# CameraConn.net
KiCad netlist of a schematic drawn in Altium Designer
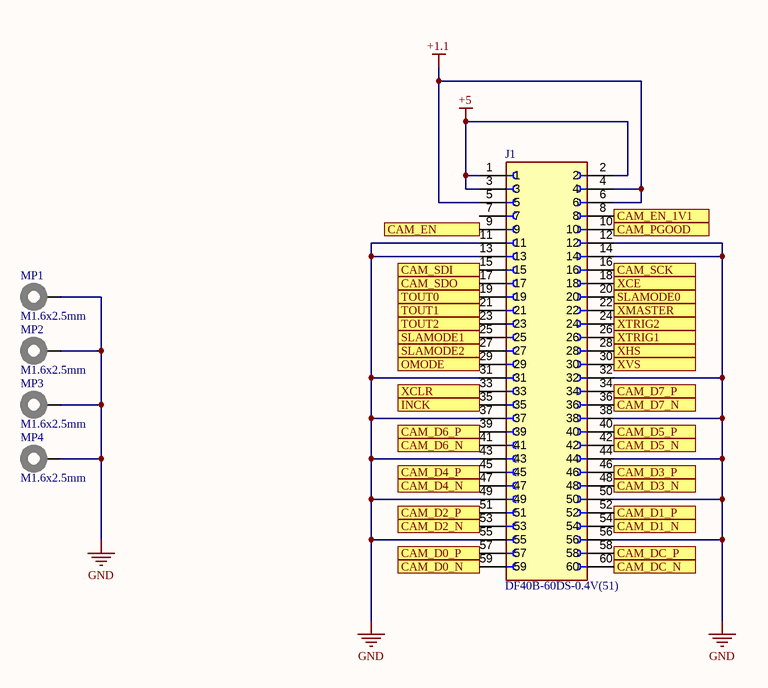
[diagram p0: CameraConn.SchDoc]

(export (version "E")
  (design (tool "Eeschema 10.0.6"))
  (components
    (comp (ref "J1")
      (value "DF40B-60DS-0.4V(51)")
      (footprint "HRS_DF40B-60DS-0.4V(51)")
      (fields (field (name "MF") "{'manufacturer': u'Hirose Electric Co Ltd'}"))
      (libsource (lib "SimulaVR") (part "DF40B-60DS-0.4V(51)"))
    )
    (comp (ref "MP1")
      (value "M1.6x2.5mm")
      (footprint "97730256330")
      (description "WA-SMSI SMT Steel Spacer, internal Thread Bottom closed, OD 3.3mm, M1.6x2.5mm")
      (fields
        (field (name "MANUFACTURER PART NUMBER") "97730256330")
        (field (name "MANUFACTURER") "Wurth Elektronik")
      )
      (libsource (lib "Altium_WA-SMSI (rev21a)") (part "97730256330"))
    )
    (comp (ref "MP2")
      (value "M1.6x2.5mm")
      (footprint "97730256330")
      (description "WA-SMSI SMT Steel Spacer, internal Thread Bottom closed, OD 3.3mm, M1.6x2.5mm")
      (fields
        (field (name "MANUFACTURER PART NUMBER") "97730256330")
        (field (name "MANUFACTURER") "Wurth Elektronik")
      )
      (libsource (lib "Altium_WA-SMSI (rev21a)") (part "97730256330"))
    )
    (comp (ref "MP3")
      (value "M1.6x2.5mm")
      (footprint "97730256330")
      (description "WA-SMSI SMT Steel Spacer, internal Thread Bottom closed, OD 3.3mm, M1.6x2.5mm")
      (fields
        (field (name "MANUFACTURER PART NUMBER") "97730256330")
        (field (name "MANUFACTURER") "Wurth Elektronik")
      )
      (libsource (lib "Altium_WA-SMSI (rev21a)") (part "97730256330"))
    )
    (comp (ref "MP4")
      (value "M1.6x2.5mm")
      (footprint "97730256330")
      (description "WA-SMSI SMT Steel Spacer, internal Thread Bottom closed, OD 3.3mm, M1.6x2.5mm")
      (fields
        (field (name "MANUFACTURER PART NUMBER") "97730256330")
        (field (name "MANUFACTURER") "Wurth Elektronik")
      )
      (libsource (lib "Altium_WA-SMSI (rev21a)") (part "97730256330"))
    )
  )
  (nets
    (net (code "1") (name "+1.1") (class "Default")
      (node (ref "J1") (pin "4") (pinfunction "4_4") (pintype "passive"))
      (node (ref "J1") (pin "5") (pinfunction "5_5") (pintype "passive"))
      (node (ref "J1") (pin "6") (pinfunction "6_6") (pintype "passive"))
    )
    (net (code "2") (name "+5") (class "Default")
      (node (ref "J1") (pin "1") (pinfunction "1_1") (pintype "passive"))
      (node (ref "J1") (pin "2") (pinfunction "2_2") (pintype "passive"))
      (node (ref "J1") (pin "3") (pinfunction "3_3") (pintype "passive"))
    )
    (net (code "3") (name "/CAM_D0_N") (class "Default")
      (node (ref "J1") (pin "59") (pinfunction "59_59") (pintype "passive"))
    )
    (net (code "4") (name "/CAM_D0_P") (class "Default")
      (node (ref "J1") (pin "57") (pinfunction "57_57") (pintype "passive"))
    )
    (net (code "5") (name "/CAM_D1_N") (class "Default")
      (node (ref "J1") (pin "54") (pinfunction "54_54") (pintype "passive"))
    )
    (net (code "6") (name "/CAM_D1_P") (class "Default")
      (node (ref "J1") (pin "52") (pinfunction "52_52") (pintype "passive"))
    )
    (net (code "7") (name "/CAM_D2_N") (class "Default")
      (node (ref "J1") (pin "53") (pinfunction "53_53") (pintype "passive"))
    )
    (net (code "8") (name "/CAM_D2_P") (class "Default")
      (node (ref "J1") (pin "51") (pinfunction "51_51") (pintype "passive"))
    )
    (net (code "9") (name "/CAM_D3_N") (class "Default")
      (node (ref "J1") (pin "48") (pinfunction "48_48") (pintype "passive"))
    )
    (net (code "10") (name "/CAM_D3_P") (class "Default")
      (node (ref "J1") (pin "46") (pinfunction "46_46") (pintype "passive"))
    )
    (net (code "11") (name "/CAM_D4_N") (class "Default")
      (node (ref "J1") (pin "47") (pinfunction "47_47") (pintype "passive"))
    )
    (net (code "12") (name "/CAM_D4_P") (class "Default")
      (node (ref "J1") (pin "45") (pinfunction "45_45") (pintype "passive"))
    )
    (net (code "13") (name "/CAM_D5_N") (class "Default")
      (node (ref "J1") (pin "42") (pinfunction "42_42") (pintype "passive"))
    )
    (net (code "14") (name "/CAM_D5_P") (class "Default")
      (node (ref "J1") (pin "40") (pinfunction "40_40") (pintype "passive"))
    )
    (net (code "15") (name "/CAM_D6_N") (class "Default")
      (node (ref "J1") (pin "41") (pinfunction "41_41") (pintype "passive"))
    )
    (net (code "16") (name "/CAM_D6_P") (class "Default")
      (node (ref "J1") (pin "39") (pinfunction "39_39") (pintype "passive"))
    )
    (net (code "17") (name "/CAM_D7_N") (class "Default")
      (node (ref "J1") (pin "36") (pinfunction "36_36") (pintype "passive"))
    )
    (net (code "18") (name "/CAM_D7_P") (class "Default")
      (node (ref "J1") (pin "34") (pinfunction "34_34") (pintype "passive"))
    )
    (net (code "19") (name "/CAM_DC_N") (class "Default")
      (node (ref "J1") (pin "60") (pinfunction "60_60") (pintype "passive"))
    )
    (net (code "20") (name "/CAM_DC_P") (class "Default")
      (node (ref "J1") (pin "58") (pinfunction "58_58") (pintype "passive"))
    )
    (net (code "21") (name "/CAM_EN") (class "Default")
      (node (ref "J1") (pin "9") (pinfunction "9_9") (pintype "passive"))
    )
    (net (code "22") (name "/CAM_EN_1V1") (class "Default")
      (node (ref "J1") (pin "8") (pinfunction "8_8") (pintype "passive"))
    )
    (net (code "23") (name "/CAM_PGOOD") (class "Default")
      (node (ref "J1") (pin "10") (pinfunction "10_10") (pintype "passive"))
    )
    (net (code "24") (name "/CAM_SCK") (class "Default")
      (node (ref "J1") (pin "16") (pinfunction "16_16") (pintype "passive"))
    )
    (net (code "25") (name "/CAM_SDI") (class "Default")
      (node (ref "J1") (pin "15") (pinfunction "15_15") (pintype "passive"))
    )
    (net (code "26") (name "/CAM_SDO") (class "Default")
      (node (ref "J1") (pin "17") (pinfunction "17_17") (pintype "passive"))
    )
    (net (code "27") (name "/INCK") (class "Default")
      (node (ref "J1") (pin "35") (pinfunction "35_35") (pintype "passive"))
    )
    (net (code "28") (name "/OMODE") (class "Default")
      (node (ref "J1") (pin "29") (pinfunction "29_29") (pintype "passive"))
    )
    (net (code "29") (name "/SLAMODE0") (class "Default")
      (node (ref "J1") (pin "20") (pinfunction "20_20") (pintype "passive"))
    )
    (net (code "30") (name "/SLAMODE1") (class "Default")
      (node (ref "J1") (pin "25") (pinfunction "25_25") (pintype "passive"))
    )
    (net (code "31") (name "/SLAMODE2") (class "Default")
      (node (ref "J1") (pin "27") (pinfunction "27_27") (pintype "passive"))
    )
    (net (code "32") (name "/TOUT0") (class "Default")
      (node (ref "J1") (pin "19") (pinfunction "19_19") (pintype "passive"))
    )
    (net (code "33") (name "/TOUT1") (class "Default")
      (node (ref "J1") (pin "21") (pinfunction "21_21") (pintype "passive"))
    )
    (net (code "34") (name "/TOUT2") (class "Default")
      (node (ref "J1") (pin "23") (pinfunction "23_23") (pintype "passive"))
    )
    (net (code "35") (name "/XCE") (class "Default")
      (node (ref "J1") (pin "18") (pinfunction "18_18") (pintype "passive"))
    )
    (net (code "36") (name "/XCLR") (class "Default")
      (node (ref "J1") (pin "33") (pinfunction "33_33") (pintype "passive"))
    )
    (net (code "37") (name "/XHS") (class "Default")
      (node (ref "J1") (pin "28") (pinfunction "28_28") (pintype "passive"))
    )
    (net (code "38") (name "/XMASTER") (class "Default")
      (node (ref "J1") (pin "22") (pinfunction "22_22") (pintype "passive"))
    )
    (net (code "39") (name "/XTRIG1") (class "Default")
      (node (ref "J1") (pin "26") (pinfunction "26_26") (pintype "passive"))
    )
    (net (code "40") (name "/XTRIG2") (class "Default")
      (node (ref "J1") (pin "24") (pinfunction "24_24") (pintype "passive"))
    )
    (net (code "41") (name "/XVS") (class "Default")
      (node (ref "J1") (pin "30") (pinfunction "30_30") (pintype "passive"))
    )
    (net (code "42") (name "GND") (class "Default")
      (node (ref "J1") (pin "11") (pinfunction "11_11") (pintype "passive"))
      (node (ref "J1") (pin "12") (pinfunction "12_12") (pintype "passive"))
      (node (ref "J1") (pin "13") (pinfunction "13_13") (pintype "passive"))
      (node (ref "J1") (pin "14") (pinfunction "14_14") (pintype "passive"))
      (node (ref "J1") (pin "31") (pinfunction "31_31") (pintype "passive"))
      (node (ref "J1") (pin "32") (pinfunction "32_32") (pintype "passive"))
      (node (ref "J1") (pin "37") (pinfunction "37_37") (pintype "passive"))
      (node (ref "J1") (pin "38") (pinfunction "38_38") (pintype "passive"))
      (node (ref "J1") (pin "43") (pinfunction "43_43") (pintype "passive"))
      (node (ref "J1") (pin "44") (pinfunction "44_44") (pintype "passive"))
      (node (ref "J1") (pin "49") (pinfunction "49_49") (pintype "passive"))
      (node (ref "J1") (pin "50") (pinfunction "50_50") (pintype "passive"))
      (node (ref "J1") (pin "55") (pinfunction "55_55") (pintype "passive"))
      (node (ref "J1") (pin "56") (pinfunction "56_56") (pintype "passive"))
      (node (ref "MP1") (pin "1") (pinfunction "1_1") (pintype "passive"))
      (node (ref "MP2") (pin "1") (pinfunction "1_1") (pintype "passive"))
      (node (ref "MP3") (pin "1") (pinfunction "1_1") (pintype "passive"))
      (node (ref "MP4") (pin "1") (pinfunction "1_1") (pintype "passive"))
    )
    (net (code "43") (name "unconnected-(J1-Pad7)") (class "Default")
      (node (ref "J1") (pin "7") (pinfunction "7_7") (pintype "passive"))
    )
  )
)
